# Filtros.net
KiCad netlist of a schematic drawn in Altium Designer
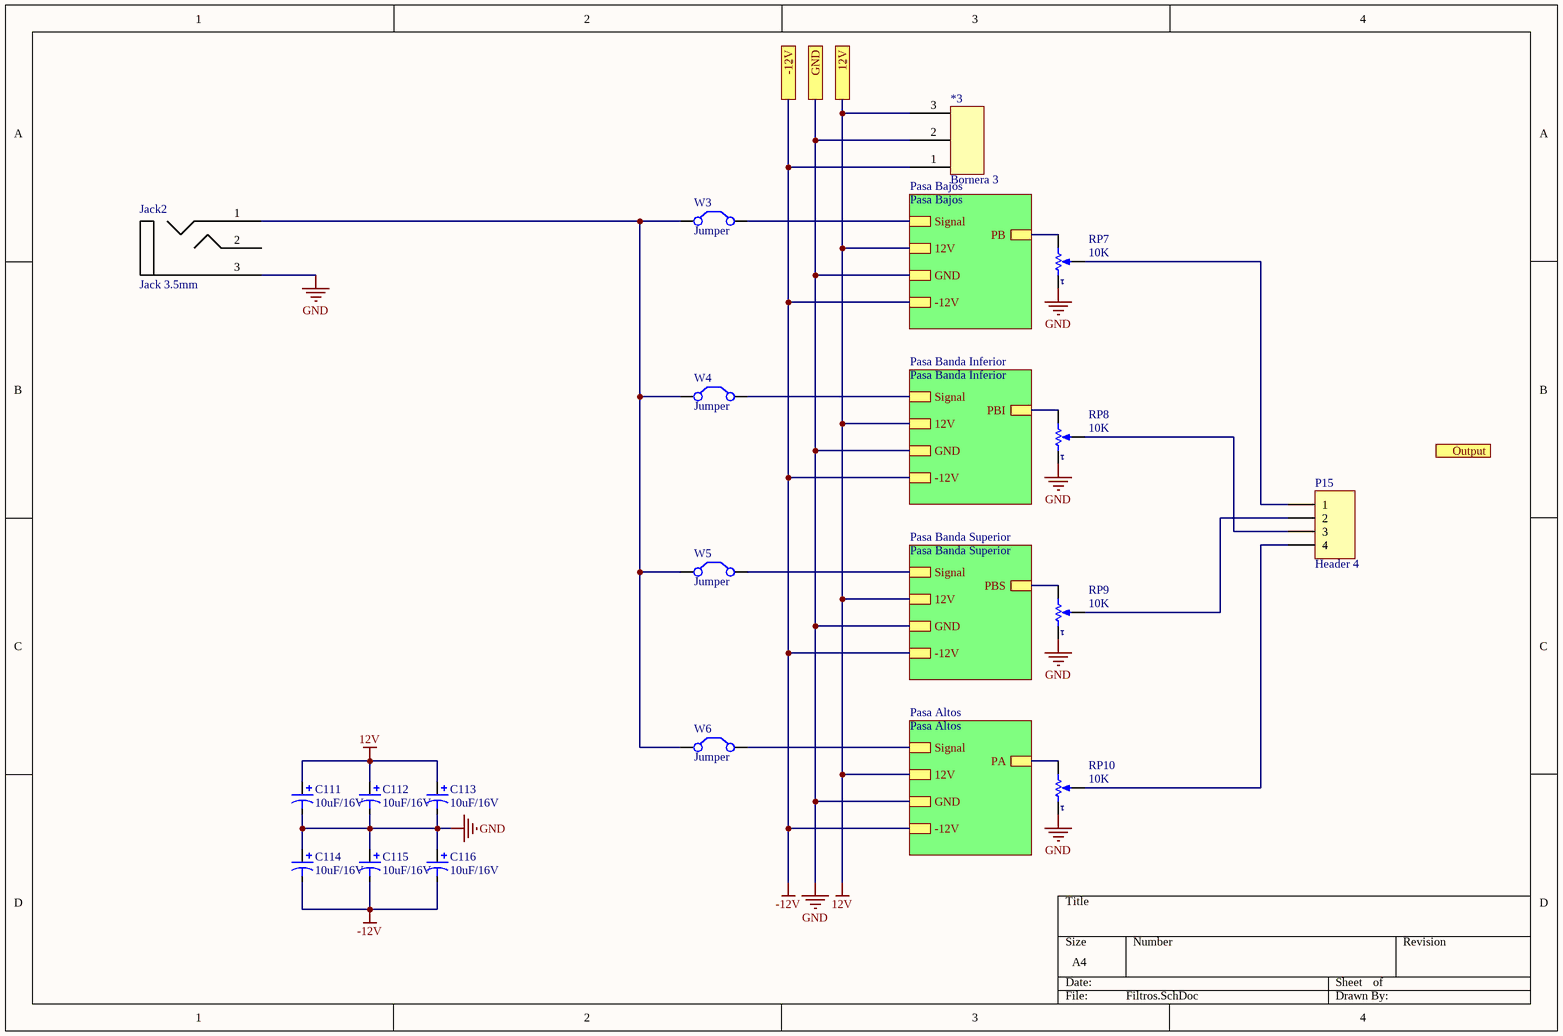
[diagram p0: Filtros.SchDoc]

(export (version "E")
  (design (tool "Eeschema 10.0.6"))
  (components
    (comp (ref "*3")
      (value "Bornera 3")
      (footprint "bornera 3")
      (libsource (lib "Userlib") (part "Bornera 3"))
    )
    (comp (ref "C111")
      (value "Cap Electrolitico Radial")
      (footprint "CAPR D250 H600 R100 mil")
      (description "Cap Electrolitico de insercion")
      (fields (field (name "VALOR") "10uF/16V"))
      (libsource (lib "RUF-Dispositivos-Grales") (part "Cap Electrolitico Radial"))
    )
    (comp (ref "C112")
      (value "Cap Electrolitico Radial")
      (footprint "CAPR D250 H600 R100 mil")
      (description "Cap Electrolitico de insercion")
      (fields (field (name "VALOR") "10uF/16V"))
      (libsource (lib "RUF-Dispositivos-Grales") (part "Cap Electrolitico Radial"))
    )
    (comp (ref "C113")
      (value "Cap Electrolitico Radial")
      (footprint "CAPR D250 H600 R100 mil")
      (description "Cap Electrolitico de insercion")
      (fields (field (name "VALOR") "10uF/16V"))
      (libsource (lib "RUF-Dispositivos-Grales") (part "Cap Electrolitico Radial"))
    )
    (comp (ref "C114")
      (value "Cap Electrolitico Radial")
      (footprint "CAPR D250 H600 R100 mil")
      (description "Cap Electrolitico de insercion")
      (fields (field (name "VALOR") "10uF/16V"))
      (libsource (lib "RUF-Dispositivos-Grales") (part "Cap Electrolitico Radial"))
    )
    (comp (ref "C115")
      (value "Cap Electrolitico Radial")
      (footprint "CAPR D250 H600 R100 mil")
      (description "Cap Electrolitico de insercion")
      (fields (field (name "VALOR") "10uF/16V"))
      (libsource (lib "RUF-Dispositivos-Grales") (part "Cap Electrolitico Radial"))
    )
    (comp (ref "C116")
      (value "Cap Electrolitico Radial")
      (footprint "CAPR D250 H600 R100 mil")
      (description "Cap Electrolitico de insercion")
      (fields (field (name "VALOR") "10uF/16V"))
      (libsource (lib "RUF-Dispositivos-Grales") (part "Cap Electrolitico Radial"))
    )
    (comp (ref "Jack2")
      (value "Jack 3.5mm")
      (footprint "jack 3.5mm")
      (libsource (lib "XR2206") (part "Jack 3.5mm"))
    )
    (comp (ref "P15")
      (value "Header 4")
      (footprint "Bornera 4")
      (description "Header, 4-Pin")
      (fields (field (name "PUBLISHER") "Altium Limited"))
      (libsource (lib "Miscellaneous Connectors") (part "Header 4"))
    )
    (comp (ref "RP7")
      (value "Trimpot")
      (footprint "Trimpot Multivuelta Vertical")
      (description "Preset")
      (fields (field (name "VALOR") "10K"))
      (libsource (lib "RUF-Dispositivos-Grales") (part "Trimpot"))
    )
    (comp (ref "RP8")
      (value "Trimpot")
      (footprint "Trimpot Multivuelta Vertical")
      (description "Preset")
      (fields (field (name "VALOR") "10K"))
      (libsource (lib "RUF-Dispositivos-Grales") (part "Trimpot"))
    )
    (comp (ref "RP9")
      (value "Trimpot")
      (footprint "Trimpot Multivuelta Vertical")
      (description "Preset")
      (fields (field (name "VALOR") "10K"))
      (libsource (lib "RUF-Dispositivos-Grales") (part "Trimpot"))
    )
    (comp (ref "RP10")
      (value "Trimpot")
      (footprint "Trimpot Multivuelta Vertical")
      (description "Preset")
      (fields (field (name "VALOR") "10K"))
      (libsource (lib "RUF-Dispositivos-Grales") (part "Trimpot"))
    )
    (comp (ref "W3")
      (value "Jumper")
      (footprint "RAD-0.2")
      (description "Jumper Wire")
      (fields (field (name "PUBLISHER") "Altium Limited"))
      (libsource (lib "Miscellaneous Devices") (part "Jumper"))
    )
    (comp (ref "W4")
      (value "Jumper")
      (footprint "RAD-0.2")
      (description "Jumper Wire")
      (fields (field (name "PUBLISHER") "Altium Limited"))
      (libsource (lib "Miscellaneous Devices") (part "Jumper"))
    )
    (comp (ref "W5")
      (value "Jumper")
      (footprint "RAD-0.2")
      (description "Jumper Wire")
      (fields (field (name "PUBLISHER") "Altium Limited"))
      (libsource (lib "Miscellaneous Devices") (part "Jumper"))
    )
    (comp (ref "W6")
      (value "Jumper")
      (footprint "RAD-0.2")
      (description "Jumper Wire")
      (fields (field (name "PUBLISHER") "Altium Limited"))
      (libsource (lib "Miscellaneous Devices") (part "Jumper"))
    )
  )
  (nets
    (net (code "1") (name "-12V") (class "Default")
      (node (ref "*3") (pin "1") (pinfunction "L_1") (pintype "passive"))
      (node (ref "C114") (pin "2") (pinfunction "2_2") (pintype "passive"))
      (node (ref "C115") (pin "2") (pinfunction "2_2") (pintype "passive"))
      (node (ref "C116") (pin "2") (pinfunction "2_2") (pintype "passive"))
    )
    (net (code "3") (name "/PA") (class "Default")
      (node (ref "RP10") (pin "2") (pinfunction "BOT_2") (pintype "passive"))
    )
    (net (code "4") (name "/PB") (class "Default")
      (node (ref "RP7") (pin "2") (pinfunction "BOT_2") (pintype "passive"))
    )
    (net (code "5") (name "/PBI") (class "Default")
      (node (ref "RP8") (pin "2") (pinfunction "BOT_2") (pintype "passive"))
    )
    (net (code "6") (name "/PBS") (class "Default")
      (node (ref "RP9") (pin "2") (pinfunction "BOT_2") (pintype "passive"))
    )
    (net (code "7") (name "/Signal") (class "Default")
      (node (ref "W6") (pin "2") (pinfunction "C2_2") (pintype "passive"))
    )
    (net (code "8") (name "/Signal_1") (class "Default")
      (node (ref "W4") (pin "2") (pinfunction "C2_2") (pintype "passive"))
    )
    (net (code "9") (name "/Signal_2") (class "Default")
      (node (ref "W3") (pin "2") (pinfunction "C2_2") (pintype "passive"))
    )
    (net (code "10") (name "/Signal_3") (class "Default")
      (node (ref "W5") (pin "2") (pinfunction "C2_2") (pintype "passive"))
    )
    (net (code "11") (name "12V") (class "Default")
      (node (ref "*3") (pin "3") (pinfunction "L_3") (pintype "passive"))
      (node (ref "C111") (pin "1") (pinfunction "1_1") (pintype "passive"))
      (node (ref "C112") (pin "1") (pinfunction "1_1") (pintype "passive"))
      (node (ref "C113") (pin "1") (pinfunction "1_1") (pintype "passive"))
    )
    (net (code "12") (name "GND") (class "Default")
      (node (ref "*3") (pin "2") (pinfunction "L_2") (pintype "passive"))
      (node (ref "C111") (pin "2") (pinfunction "2_2") (pintype "passive"))
      (node (ref "C112") (pin "2") (pinfunction "2_2") (pintype "passive"))
      (node (ref "C113") (pin "2") (pinfunction "2_2") (pintype "passive"))
      (node (ref "C114") (pin "1") (pinfunction "1_1") (pintype "passive"))
      (node (ref "C115") (pin "1") (pinfunction "1_1") (pintype "passive"))
      (node (ref "C116") (pin "1") (pinfunction "1_1") (pintype "passive"))
      (node (ref "Jack2") (pin "3") (pinfunction "Gnd_3") (pintype "passive"))
      (node (ref "RP10") (pin "1") (pinfunction "TOP_1") (pintype "passive"))
      (node (ref "RP7") (pin "1") (pinfunction "TOP_1") (pintype "passive"))
      (node (ref "RP8") (pin "1") (pinfunction "TOP_1") (pintype "passive"))
      (node (ref "RP9") (pin "1") (pinfunction "TOP_1") (pintype "passive"))
    )
    (net (code "13") (name "Net-(Jack2-R)") (class "Default")
      (node (ref "Jack2") (pin "1") (pinfunction "R_1") (pintype "passive"))
      (node (ref "W3") (pin "1") (pinfunction "C1_1") (pintype "passive"))
      (node (ref "W4") (pin "1") (pinfunction "C1_1") (pintype "passive"))
      (node (ref "W5") (pin "1") (pinfunction "C1_1") (pintype "passive"))
      (node (ref "W6") (pin "1") (pinfunction "C1_1") (pintype "passive"))
    )
    (net (code "14") (name "Net-(RP7-TAP)") (class "Default")
      (node (ref "P15") (pin "1") (pinfunction "1_1") (pintype "passive"))
      (node (ref "RP7") (pin "3") (pinfunction "TAP_3") (pintype "passive"))
    )
    (net (code "15") (name "Net-(RP8-TAP)") (class "Default")
      (node (ref "P15") (pin "3") (pinfunction "3_3") (pintype "passive"))
      (node (ref "RP8") (pin "3") (pinfunction "TAP_3") (pintype "passive"))
    )
    (net (code "16") (name "Net-(RP9-TAP)") (class "Default")
      (node (ref "P15") (pin "2") (pinfunction "2_2") (pintype "passive"))
      (node (ref "RP9") (pin "3") (pinfunction "TAP_3") (pintype "passive"))
    )
    (net (code "17") (name "Net-(RP10-TAP)") (class "Default")
      (node (ref "P15") (pin "4") (pinfunction "4_4") (pintype "passive"))
      (node (ref "RP10") (pin "3") (pinfunction "TAP_3") (pintype "passive"))
    )
    (net (code "18") (name "unconnected-(Jack2-L-Pad2)") (class "Default")
      (node (ref "Jack2") (pin "2") (pinfunction "L_2") (pintype "passive"))
    )
  )
)
